# Interfaces.net
KiCad netlist of a schematic drawn in Altium Designer
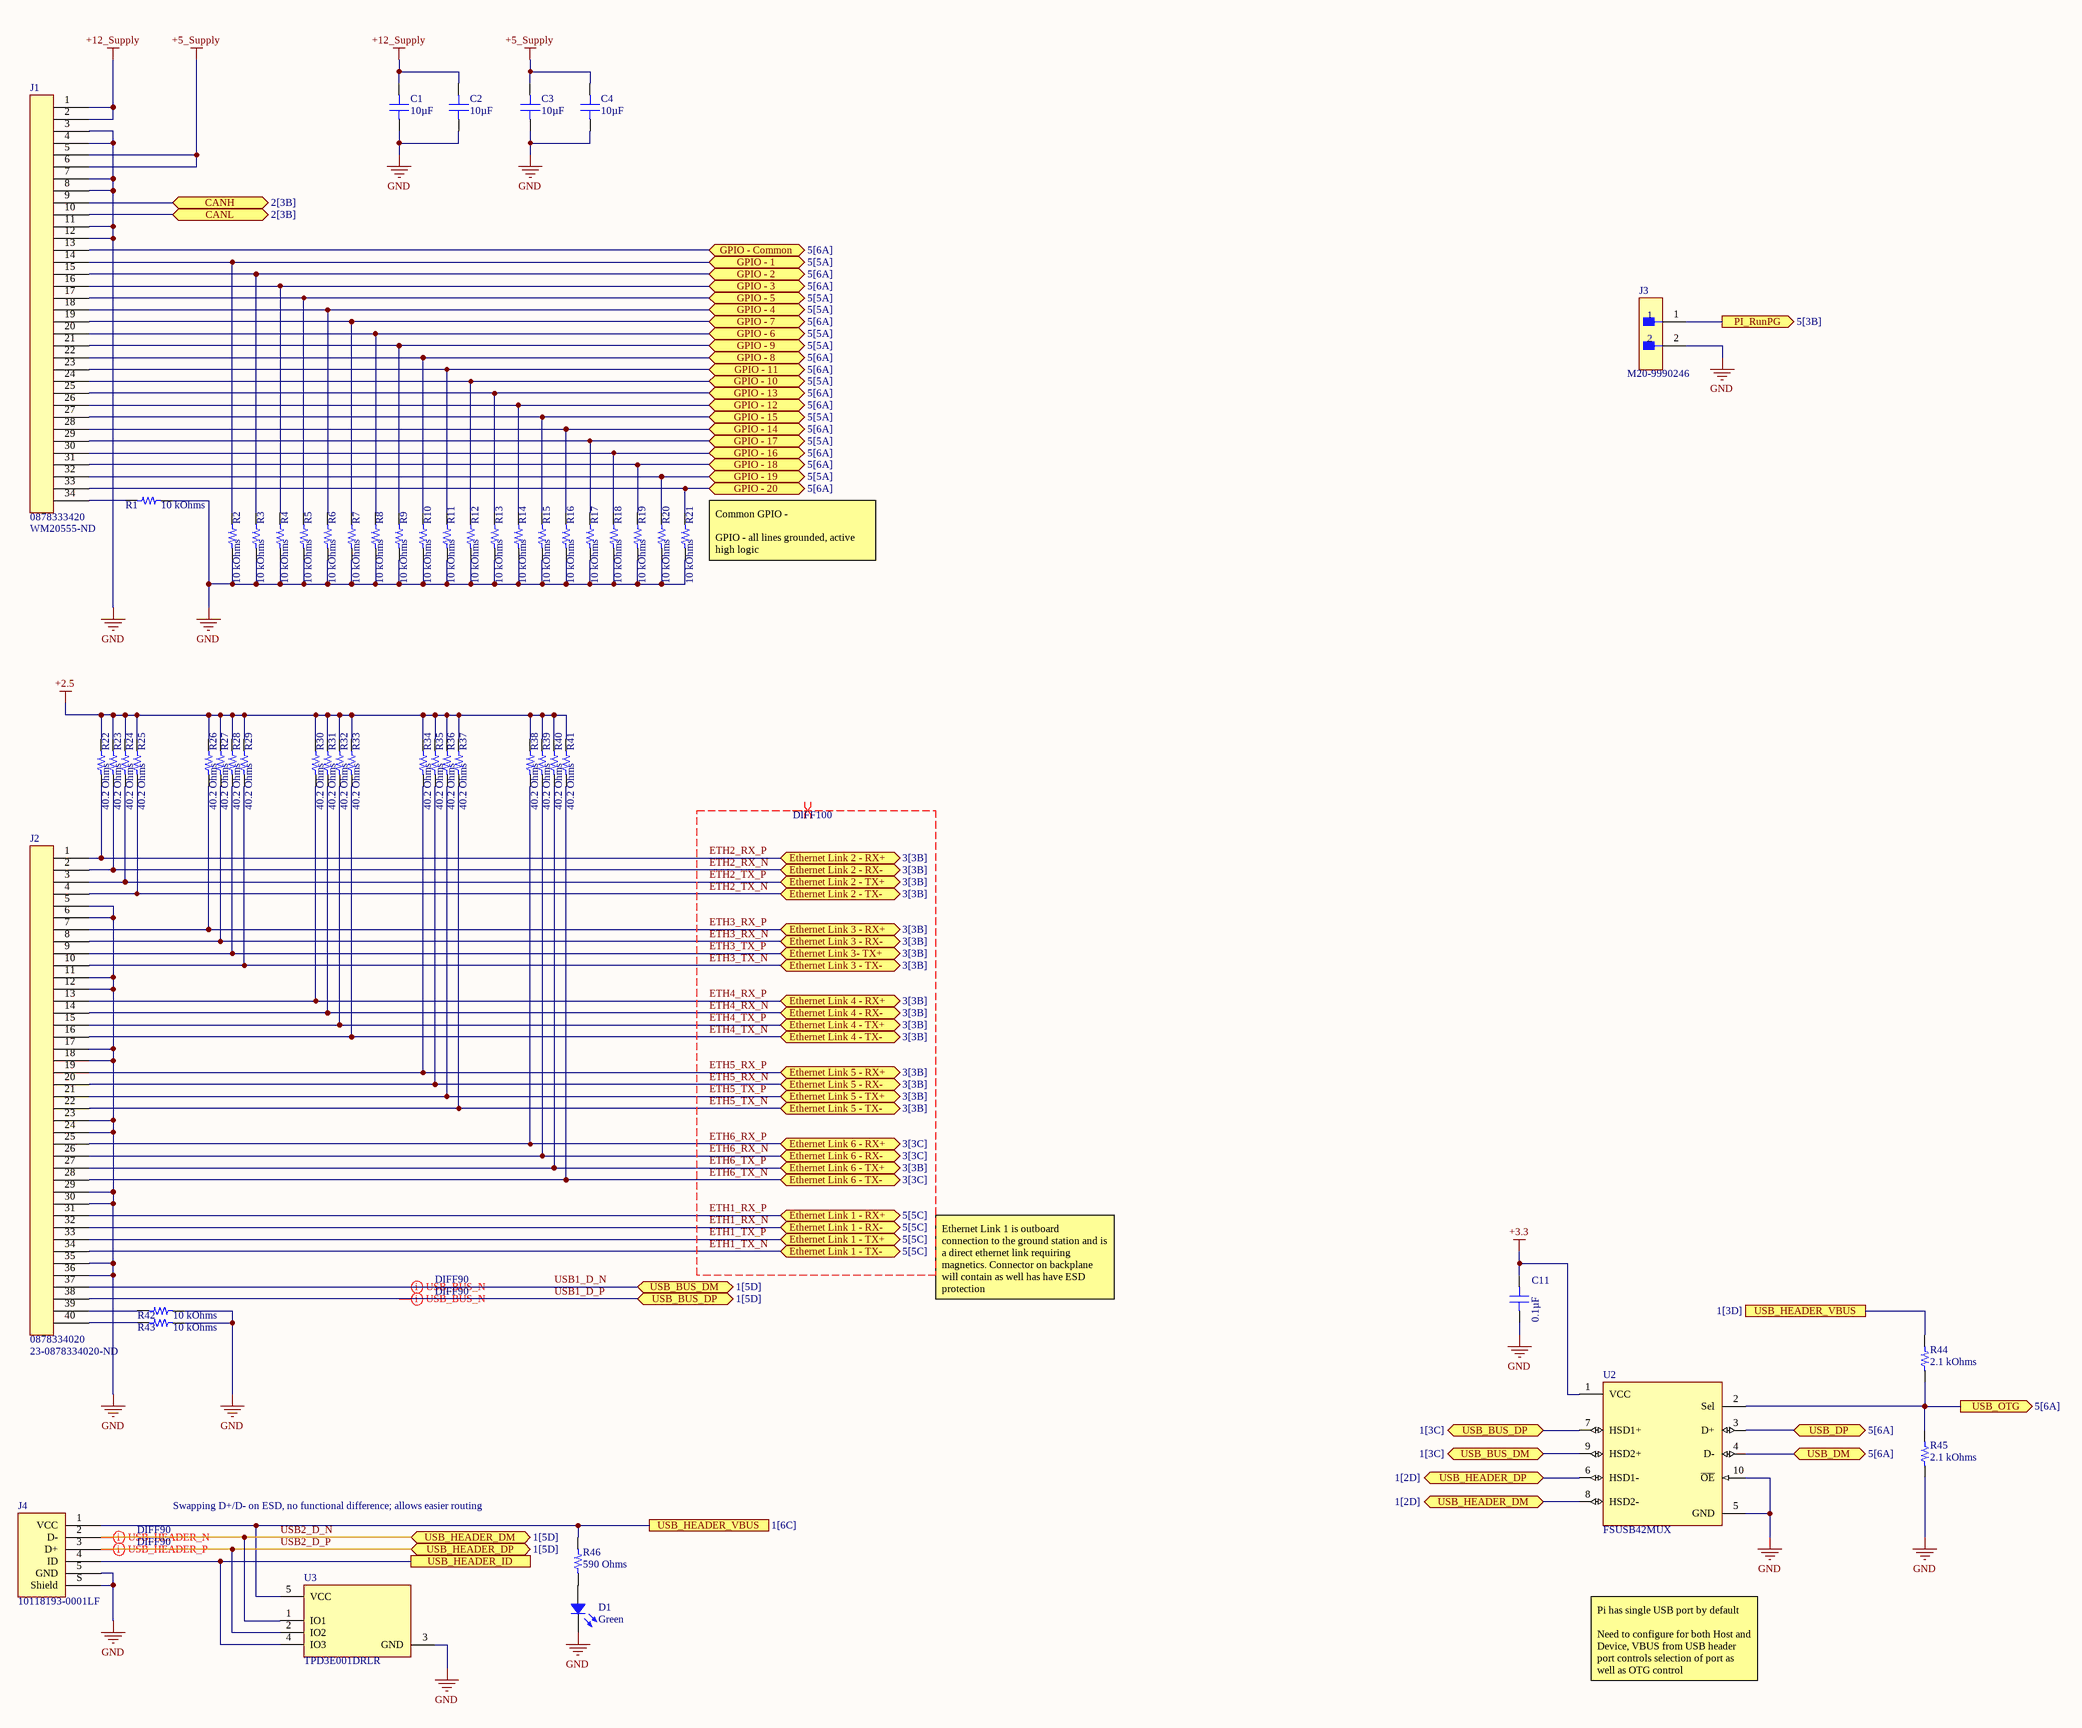
[diagram p0: Interfaces.SchDoc]

(export (version "E")
  (design (tool "Eeschema 10.0.6"))
  (components
    (comp (ref "C1")
      (value "10µF")
      (footprint "CAP 0805_2012")
      (description "CAP CER 10UF 16V X5R 0805")
      (fields (field (name "PART NUMBER") "CC0805KKX5R7BB106") (field (name "MANUFACTURER") "Yageo"))
      (libsource (lib "Celestial Altium Library - altium_library") (part "Capacitor"))
    )
    (comp (ref "C2")
      (value "10µF")
      (footprint "CAP 0805_2012")
      (description "CAP CER 10UF 16V X5R 0805")
      (fields (field (name "PART NUMBER") "CC0805KKX5R7BB106") (field (name "MANUFACTURER") "Yageo"))
      (libsource (lib "Celestial Altium Library - altium_library") (part "Capacitor"))
    )
    (comp (ref "C3")
      (value "10µF")
      (footprint "CAP 0805_2012")
      (description "CAP CER 10UF 16V X5R 0805")
      (fields (field (name "PART NUMBER") "CC0805KKX5R7BB106") (field (name "MANUFACTURER") "Yageo"))
      (libsource (lib "Celestial Altium Library - altium_library") (part "Capacitor"))
    )
    (comp (ref "C4")
      (value "10µF")
      (footprint "CAP 0805_2012")
      (description "CAP CER 10UF 16V X5R 0805")
      (fields (field (name "PART NUMBER") "CC0805KKX5R7BB106") (field (name "MANUFACTURER") "Yageo"))
      (libsource (lib "Celestial Altium Library - altium_library") (part "Capacitor"))
    )
    (comp (ref "C11")
      (value "0.1µF")
      (footprint "CAP 0603_1608")
      (description "CAP CER 0.1UF 25V X7R 0603")
      (fields
        (field (name "PART NUMBER") "CL10B104KA8WPNC")
        (field (name "MANUFACTURER") "Samsung Electro-Mechanics")
      )
      (libsource (lib "Celestial Altium Library - altium_library") (part "Capacitor"))
    )
    (comp (ref "D1")
      (value "Green")
      (footprint "LED 0603_1608 GREEN")
      (description "LED GREEN CLEAR CHIP SMD")
      (fields (field (name "PART NUMBER") "LTST-C193KGKT-5A") (field (name "MANUFACTURER") "Lite-On Inc."))
      (libsource (lib "Celestial Altium Library - altium_library") (part "LED"))
    )
    (comp (ref "J1")
      (value "0878333420")
      (footprint "0878333420")
      (fields (field (name "SUPPLIER PART NUMBER 1") "WM20555-ND"))
      (libsource (lib "HAB_Connectors") (part "0878333420"))
    )
    (comp (ref "J2")
      (value "0878334020")
      (footprint "0878334020")
      (fields (field (name "SUPPLIER PART NUMBER 1") "23-0878334020-ND"))
      (libsource (lib "HAB_Connectors") (part "0878334020"))
    )
    (comp (ref "J3")
      (value "M20-9990246")
      (footprint "FP-M20-9990246-MFG")
      (description "CONN HEADER VERT 2POS 2.54MM")
      (fields
        (field (name "OCTOPART") "https://octopart.com/m20-9990246-harwin-2590635")
        (field (name "MANUFACTURER") "Harwin")
      )
      (libsource (lib "Altium Content Vault") (part "3bc925449376181038e59eaffc5286c"))
    )
    (comp (ref "J4")
      (value "10118193-0001LF")
      (footprint "FCI USB 10118193-0001LF")
      (description "CONN RCPT USB2.0 MICRO B SMD R/A")
      (fields (field (name "MANUFACTURER") "Amphenol ICC (FCI)"))
      (libsource (lib "Celestial Altium Library - altium_library") (part "USB 2.0 Type B Micro"))
    )
    (comp (ref "R1")
      (value "10 kOhms")
      (footprint "RES 0603_1608")
      (description "RES 10K OHM 5% 1/10W 0603")
      (fields
        (field (name "PART NUMBER") "RMCF0603JT10K0")
        (field (name "MANUFACTURER") "Stackpole Electronics Inc")
      )
      (libsource (lib "Celestial Altium Library - altium_library") (part "Resistor"))
    )
    (comp (ref "R2")
      (value "10 kOhms")
      (footprint "RES 0603_1608")
      (description "RES 10K OHM 5% 1/10W 0603")
      (fields
        (field (name "PART NUMBER") "RMCF0603JT10K0")
        (field (name "MANUFACTURER") "Stackpole Electronics Inc")
      )
      (libsource (lib "Celestial Altium Library - altium_library") (part "Resistor"))
    )
    (comp (ref "R3")
      (value "10 kOhms")
      (footprint "RES 0603_1608")
      (description "RES 10K OHM 5% 1/10W 0603")
      (fields
        (field (name "PART NUMBER") "RMCF0603JT10K0")
        (field (name "MANUFACTURER") "Stackpole Electronics Inc")
      )
      (libsource (lib "Celestial Altium Library - altium_library") (part "Resistor"))
    )
    (comp (ref "R4")
      (value "10 kOhms")
      (footprint "RES 0603_1608")
      (description "RES 10K OHM 5% 1/10W 0603")
      (fields
        (field (name "PART NUMBER") "RMCF0603JT10K0")
        (field (name "MANUFACTURER") "Stackpole Electronics Inc")
      )
      (libsource (lib "Celestial Altium Library - altium_library") (part "Resistor"))
    )
    (comp (ref "R5")
      (value "10 kOhms")
      (footprint "RES 0603_1608")
      (description "RES 10K OHM 5% 1/10W 0603")
      (fields
        (field (name "PART NUMBER") "RMCF0603JT10K0")
        (field (name "MANUFACTURER") "Stackpole Electronics Inc")
      )
      (libsource (lib "Celestial Altium Library - altium_library") (part "Resistor"))
    )
    (comp (ref "R6")
      (value "10 kOhms")
      (footprint "RES 0603_1608")
      (description "RES 10K OHM 5% 1/10W 0603")
      (fields
        (field (name "PART NUMBER") "RMCF0603JT10K0")
        (field (name "MANUFACTURER") "Stackpole Electronics Inc")
      )
      (libsource (lib "Celestial Altium Library - altium_library") (part "Resistor"))
    )
    (comp (ref "R7")
      (value "10 kOhms")
      (footprint "RES 0603_1608")
      (description "RES 10K OHM 5% 1/10W 0603")
      (fields
        (field (name "PART NUMBER") "RMCF0603JT10K0")
        (field (name "MANUFACTURER") "Stackpole Electronics Inc")
      )
      (libsource (lib "Celestial Altium Library - altium_library") (part "Resistor"))
    )
    (comp (ref "R8")
      (value "10 kOhms")
      (footprint "RES 0603_1608")
      (description "RES 10K OHM 5% 1/10W 0603")
      (fields
        (field (name "PART NUMBER") "RMCF0603JT10K0")
        (field (name "MANUFACTURER") "Stackpole Electronics Inc")
      )
      (libsource (lib "Celestial Altium Library - altium_library") (part "Resistor"))
    )
    (comp (ref "R9")
      (value "10 kOhms")
      (footprint "RES 0603_1608")
      (description "RES 10K OHM 5% 1/10W 0603")
      (fields
        (field (name "PART NUMBER") "RMCF0603JT10K0")
        (field (name "MANUFACTURER") "Stackpole Electronics Inc")
      )
      (libsource (lib "Celestial Altium Library - altium_library") (part "Resistor"))
    )
    (comp (ref "R10")
      (value "10 kOhms")
      (footprint "RES 0603_1608")
      (description "RES 10K OHM 5% 1/10W 0603")
      (fields
        (field (name "PART NUMBER") "RMCF0603JT10K0")
        (field (name "MANUFACTURER") "Stackpole Electronics Inc")
      )
      (libsource (lib "Celestial Altium Library - altium_library") (part "Resistor"))
    )
    (comp (ref "R11")
      (value "10 kOhms")
      (footprint "RES 0603_1608")
      (description "RES 10K OHM 5% 1/10W 0603")
      (fields
        (field (name "PART NUMBER") "RMCF0603JT10K0")
        (field (name "MANUFACTURER") "Stackpole Electronics Inc")
      )
      (libsource (lib "Celestial Altium Library - altium_library") (part "Resistor"))
    )
    (comp (ref "R12")
      (value "10 kOhms")
      (footprint "RES 0603_1608")
      (description "RES 10K OHM 5% 1/10W 0603")
      (fields
        (field (name "PART NUMBER") "RMCF0603JT10K0")
        (field (name "MANUFACTURER") "Stackpole Electronics Inc")
      )
      (libsource (lib "Celestial Altium Library - altium_library") (part "Resistor"))
    )
    (comp (ref "R13")
      (value "10 kOhms")
      (footprint "RES 0603_1608")
      (description "RES 10K OHM 5% 1/10W 0603")
      (fields
        (field (name "PART NUMBER") "RMCF0603JT10K0")
        (field (name "MANUFACTURER") "Stackpole Electronics Inc")
      )
      (libsource (lib "Celestial Altium Library - altium_library") (part "Resistor"))
    )
    (comp (ref "R14")
      (value "10 kOhms")
      (footprint "RES 0603_1608")
      (description "RES 10K OHM 5% 1/10W 0603")
      (fields
        (field (name "PART NUMBER") "RMCF0603JT10K0")
        (field (name "MANUFACTURER") "Stackpole Electronics Inc")
      )
      (libsource (lib "Celestial Altium Library - altium_library") (part "Resistor"))
    )
    (comp (ref "R15")
      (value "10 kOhms")
      (footprint "RES 0603_1608")
      (description "RES 10K OHM 5% 1/10W 0603")
      (fields
        (field (name "PART NUMBER") "RMCF0603JT10K0")
        (field (name "MANUFACTURER") "Stackpole Electronics Inc")
      )
      (libsource (lib "Celestial Altium Library - altium_library") (part "Resistor"))
    )
    (comp (ref "R16")
      (value "10 kOhms")
      (footprint "RES 0603_1608")
      (description "RES 10K OHM 5% 1/10W 0603")
      (fields
        (field (name "PART NUMBER") "RMCF0603JT10K0")
        (field (name "MANUFACTURER") "Stackpole Electronics Inc")
      )
      (libsource (lib "Celestial Altium Library - altium_library") (part "Resistor"))
    )
    (comp (ref "R17")
      (value "10 kOhms")
      (footprint "RES 0603_1608")
      (description "RES 10K OHM 5% 1/10W 0603")
      (fields
        (field (name "PART NUMBER") "RMCF0603JT10K0")
        (field (name "MANUFACTURER") "Stackpole Electronics Inc")
      )
      (libsource (lib "Celestial Altium Library - altium_library") (part "Resistor"))
    )
    (comp (ref "R18")
      (value "10 kOhms")
      (footprint "RES 0603_1608")
      (description "RES 10K OHM 5% 1/10W 0603")
      (fields
        (field (name "PART NUMBER") "RMCF0603JT10K0")
        (field (name "MANUFACTURER") "Stackpole Electronics Inc")
      )
      (libsource (lib "Celestial Altium Library - altium_library") (part "Resistor"))
    )
    (comp (ref "R19")
      (value "10 kOhms")
      (footprint "RES 0603_1608")
      (description "RES 10K OHM 5% 1/10W 0603")
      (fields
        (field (name "PART NUMBER") "RMCF0603JT10K0")
        (field (name "MANUFACTURER") "Stackpole Electronics Inc")
      )
      (libsource (lib "Celestial Altium Library - altium_library") (part "Resistor"))
    )
    (comp (ref "R20")
      (value "10 kOhms")
      (footprint "RES 0603_1608")
      (description "RES 10K OHM 5% 1/10W 0603")
      (fields
        (field (name "PART NUMBER") "RMCF0603JT10K0")
        (field (name "MANUFACTURER") "Stackpole Electronics Inc")
      )
      (libsource (lib "Celestial Altium Library - altium_library") (part "Resistor"))
    )
    (comp (ref "R21")
      (value "10 kOhms")
      (footprint "RES 0603_1608")
      (description "RES 10K OHM 5% 1/10W 0603")
      (fields
        (field (name "PART NUMBER") "RMCF0603JT10K0")
        (field (name "MANUFACTURER") "Stackpole Electronics Inc")
      )
      (libsource (lib "Celestial Altium Library - altium_library") (part "Resistor"))
    )
    (comp (ref "R22")
      (value "40.2 Ohms")
      (footprint "RES 0603_1608")
      (description "RES SMD 40.2 OHM 1% 1/10W 0603")
      (fields (field (name "PART NUMBER") "RC0603FR-0740R2L") (field (name "MANUFACTURER") "Yageo"))
      (libsource (lib "Celestial Altium Library - altium_library") (part "Resistor"))
    )
    (comp (ref "R23")
      (value "40.2 Ohms")
      (footprint "RES 0603_1608")
      (description "RES SMD 40.2 OHM 1% 1/10W 0603")
      (fields (field (name "PART NUMBER") "RC0603FR-0740R2L") (field (name "MANUFACTURER") "Yageo"))
      (libsource (lib "Celestial Altium Library - altium_library") (part "Resistor"))
    )
    (comp (ref "R24")
      (value "40.2 Ohms")
      (footprint "RES 0603_1608")
      (description "RES SMD 40.2 OHM 1% 1/10W 0603")
      (fields (field (name "PART NUMBER") "RC0603FR-0740R2L") (field (name "MANUFACTURER") "Yageo"))
      (libsource (lib "Celestial Altium Library - altium_library") (part "Resistor"))
    )
    (comp (ref "R25")
      (value "40.2 Ohms")
      (footprint "RES 0603_1608")
      (description "RES SMD 40.2 OHM 1% 1/10W 0603")
      (fields (field (name "PART NUMBER") "RC0603FR-0740R2L") (field (name "MANUFACTURER") "Yageo"))
      (libsource (lib "Celestial Altium Library - altium_library") (part "Resistor"))
    )
    (comp (ref "R26")
      (value "40.2 Ohms")
      (footprint "RES 0603_1608")
      (description "RES SMD 40.2 OHM 1% 1/10W 0603")
      (fields (field (name "PART NUMBER") "RC0603FR-0740R2L") (field (name "MANUFACTURER") "Yageo"))
      (libsource (lib "Celestial Altium Library - altium_library") (part "Resistor"))
    )
    (comp (ref "R27")
      (value "40.2 Ohms")
      (footprint "RES 0603_1608")
      (description "RES SMD 40.2 OHM 1% 1/10W 0603")
      (fields (field (name "PART NUMBER") "RC0603FR-0740R2L") (field (name "MANUFACTURER") "Yageo"))
      (libsource (lib "Celestial Altium Library - altium_library") (part "Resistor"))
    )
    (comp (ref "R28")
      (value "40.2 Ohms")
      (footprint "RES 0603_1608")
      (description "RES SMD 40.2 OHM 1% 1/10W 0603")
      (fields (field (name "PART NUMBER") "RC0603FR-0740R2L") (field (name "MANUFACTURER") "Yageo"))
      (libsource (lib "Celestial Altium Library - altium_library") (part "Resistor"))
    )
    (comp (ref "R29")
      (value "40.2 Ohms")
      (footprint "RES 0603_1608")
      (description "RES SMD 40.2 OHM 1% 1/10W 0603")
      (fields (field (name "PART NUMBER") "RC0603FR-0740R2L") (field (name "MANUFACTURER") "Yageo"))
      (libsource (lib "Celestial Altium Library - altium_library") (part "Resistor"))
    )
    (comp (ref "R30")
      (value "40.2 Ohms")
      (footprint "RES 0603_1608")
      (description "RES SMD 40.2 OHM 1% 1/10W 0603")
      (fields (field (name "PART NUMBER") "RC0603FR-0740R2L") (field (name "MANUFACTURER") "Yageo"))
      (libsource (lib "Celestial Altium Library - altium_library") (part "Resistor"))
    )
    (comp (ref "R31")
      (value "40.2 Ohms")
      (footprint "RES 0603_1608")
      (description "RES SMD 40.2 OHM 1% 1/10W 0603")
      (fields (field (name "PART NUMBER") "RC0603FR-0740R2L") (field (name "MANUFACTURER") "Yageo"))
      (libsource (lib "Celestial Altium Library - altium_library") (part "Resistor"))
    )
    (comp (ref "R32")
      (value "40.2 Ohms")
      (footprint "RES 0603_1608")
      (description "RES SMD 40.2 OHM 1% 1/10W 0603")
      (fields (field (name "PART NUMBER") "RC0603FR-0740R2L") (field (name "MANUFACTURER") "Yageo"))
      (libsource (lib "Celestial Altium Library - altium_library") (part "Resistor"))
    )
    (comp (ref "R33")
      (value "40.2 Ohms")
      (footprint "RES 0603_1608")
      (description "RES SMD 40.2 OHM 1% 1/10W 0603")
      (fields (field (name "PART NUMBER") "RC0603FR-0740R2L") (field (name "MANUFACTURER") "Yageo"))
      (libsource (lib "Celestial Altium Library - altium_library") (part "Resistor"))
    )
    (comp (ref "R34")
      (value "40.2 Ohms")
      (footprint "RES 0603_1608")
      (description "RES SMD 40.2 OHM 1% 1/10W 0603")
      (fields (field (name "PART NUMBER") "RC0603FR-0740R2L") (field (name "MANUFACTURER") "Yageo"))
      (libsource (lib "Celestial Altium Library - altium_library") (part "Resistor"))
    )
    (comp (ref "R35")
      (value "40.2 Ohms")
      (footprint "RES 0603_1608")
      (description "RES SMD 40.2 OHM 1% 1/10W 0603")
      (fields (field (name "PART NUMBER") "RC0603FR-0740R2L") (field (name "MANUFACTURER") "Yageo"))
      (libsource (lib "Celestial Altium Library - altium_library") (part "Resistor"))
    )
    (comp (ref "R36")
      (value "40.2 Ohms")
      (footprint "RES 0603_1608")
      (description "RES SMD 40.2 OHM 1% 1/10W 0603")
      (fields (field (name "PART NUMBER") "RC0603FR-0740R2L") (field (name "MANUFACTURER") "Yageo"))
      (libsource (lib "Celestial Altium Library - altium_library") (part "Resistor"))
    )
    (comp (ref "R37")
      (value "40.2 Ohms")
      (footprint "RES 0603_1608")
      (description "RES SMD 40.2 OHM 1% 1/10W 0603")
      (fields (field (name "PART NUMBER") "RC0603FR-0740R2L") (field (name "MANUFACTURER") "Yageo"))
      (libsource (lib "Celestial Altium Library - altium_library") (part "Resistor"))
    )
    (comp (ref "R38")
      (value "40.2 Ohms")
      (footprint "RES 0603_1608")
      (description "RES SMD 40.2 OHM 1% 1/10W 0603")
      (fields (field (name "PART NUMBER") "RC0603FR-0740R2L") (field (name "MANUFACTURER") "Yageo"))
      (libsource (lib "Celestial Altium Library - altium_library") (part "Resistor"))
    )
    (comp (ref "R39")
      (value "40.2 Ohms")
      (footprint "RES 0603_1608")
      (description "RES SMD 40.2 OHM 1% 1/10W 0603")
      (fields (field (name "PART NUMBER") "RC0603FR-0740R2L") (field (name "MANUFACTURER") "Yageo"))
      (libsource (lib "Celestial Altium Library - altium_library") (part "Resistor"))
    )
    (comp (ref "R40")
      (value "40.2 Ohms")
      (footprint "RES 0603_1608")
      (description "RES SMD 40.2 OHM 1% 1/10W 0603")
      (fields (field (name "PART NUMBER") "RC0603FR-0740R2L") (field (name "MANUFACTURER") "Yageo"))
      (libsource (lib "Celestial Altium Library - altium_library") (part "Resistor"))
    )
    (comp (ref "R41")
      (value "40.2 Ohms")
      (footprint "RES 0603_1608")
      (description "RES SMD 40.2 OHM 1% 1/10W 0603")
      (fields (field (name "PART NUMBER") "RC0603FR-0740R2L") (field (name "MANUFACTURER") "Yageo"))
      (libsource (lib "Celestial Altium Library - altium_library") (part "Resistor"))
    )
    (comp (ref "R42")
      (value "10 kOhms")
      (footprint "RES 0603_1608")
      (description "RES 10K OHM 5% 1/10W 0603")
      (fields
        (field (name "PART NUMBER") "RMCF0603JT10K0")
        (field (name "MANUFACTURER") "Stackpole Electronics Inc")
      )
      (libsource (lib "Celestial Altium Library - altium_library") (part "Resistor"))
    )
    (comp (ref "R43")
      (value "10 kOhms")
      (footprint "RES 0603_1608")
      (description "RES 10K OHM 5% 1/10W 0603")
      (fields
        (field (name "PART NUMBER") "RMCF0603JT10K0")
        (field (name "MANUFACTURER") "Stackpole Electronics Inc")
      )
      (libsource (lib "Celestial Altium Library - altium_library") (part "Resistor"))
    )
    (comp (ref "R44")
      (value "2.1 kOhms")
      (footprint "RES 0603_1608")
      (description "RES 2.1K OHM 1% 1/10W 0603")
      (fields
        (field (name "PART NUMBER") "RMCF0603FT2K10")
        (field (name "MANUFACTURER") "Stackpole Electronics Inc")
      )
      (libsource (lib "Celestial Altium Library - altium_library") (part "Resistor"))
    )
    (comp (ref "R45")
      (value "2.1 kOhms")
      (footprint "RES 0603_1608")
      (description "RES 2.1K OHM 1% 1/10W 0603")
      (fields
        (field (name "PART NUMBER") "RMCF0603FT2K10")
        (field (name "MANUFACTURER") "Stackpole Electronics Inc")
      )
      (libsource (lib "Celestial Altium Library - altium_library") (part "Resistor"))
    )
    (comp (ref "R46")
      (value "590 Ohms")
      (footprint "RES 0603_1608")
      (description "RES 590 OHM 1% 1/10W 0603")
      (fields
        (field (name "PART NUMBER") "RMCF0603FT590R")
        (field (name "MANUFACTURER") "Stackpole Electronics Inc")
      )
      (libsource (lib "Celestial Altium Library - altium_library") (part "Resistor"))
    )
    (comp (ref "U2")
      (value "FSUSB42MUX")
      (footprint "FP-846AP-MFG")
      (description "IC USB SWITCH DPDT 10MSOP")
      (fields (field (name "VOLTAGE") "4.3V"))
      (libsource (lib "Altium Content Vault") (part "e0bd5e1b4e0e4edc77f3356c64bf8f9"))
    )
    (comp (ref "U3")
      (value "TPD3E001DRLR")
      (footprint "FP-DRL0005A-MFG")
      (description "TVS DIODE 5.5V SOT5")
      (libsource (lib "Altium Content Vault") (part "867ba43d99b3a33c275ad84274a843c"))
    )
  )
  (nets
    (net (code "1") (name "+2.5") (class "Default")
      (node (ref "R22") (pin "2") (pinfunction "2_2") (pintype "passive"))
      (node (ref "R23") (pin "2") (pinfunction "2_2") (pintype "passive"))
      (node (ref "R24") (pin "2") (pinfunction "2_2") (pintype "passive"))
      (node (ref "R25") (pin "2") (pinfunction "2_2") (pintype "passive"))
      (node (ref "R26") (pin "2") (pinfunction "2_2") (pintype "passive"))
      (node (ref "R27") (pin "2") (pinfunction "2_2") (pintype "passive"))
      (node (ref "R28") (pin "2") (pinfunction "2_2") (pintype "passive"))
      (node (ref "R29") (pin "2") (pinfunction "2_2") (pintype "passive"))
      (node (ref "R30") (pin "2") (pinfunction "2_2") (pintype "passive"))
      (node (ref "R31") (pin "2") (pinfunction "2_2") (pintype "passive"))
      (node (ref "R32") (pin "2") (pinfunction "2_2") (pintype "passive"))
      (node (ref "R33") (pin "2") (pinfunction "2_2") (pintype "passive"))
      (node (ref "R34") (pin "2") (pinfunction "2_2") (pintype "passive"))
      (node (ref "R35") (pin "2") (pinfunction "2_2") (pintype "passive"))
      (node (ref "R36") (pin "2") (pinfunction "2_2") (pintype "passive"))
      (node (ref "R37") (pin "2") (pinfunction "2_2") (pintype "passive"))
      (node (ref "R38") (pin "2") (pinfunction "2_2") (pintype "passive"))
      (node (ref "R39") (pin "2") (pinfunction "2_2") (pintype "passive"))
      (node (ref "R40") (pin "2") (pinfunction "2_2") (pintype "passive"))
      (node (ref "R41") (pin "2") (pinfunction "2_2") (pintype "passive"))
    )
    (net (code "2") (name "+3.3") (class "Default")
      (node (ref "C11") (pin "2") (pinfunction "2_2") (pintype "passive"))
      (node (ref "U2") (pin "1") (pinfunction "VCC_1") (pintype "power_in"))
    )
    (net (code "3") (name "+5_Supply") (class "Default")
      (node (ref "C3") (pin "2") (pinfunction "2_2") (pintype "passive"))
      (node (ref "C4") (pin "2") (pinfunction "2_2") (pintype "passive"))
      (node (ref "J1") (pin "5") (pintype "passive"))
      (node (ref "J1") (pin "6") (pintype "passive"))
    )
    (net (code "4") (name "+12_Supply") (class "Default")
      (node (ref "C1") (pin "2") (pinfunction "2_2") (pintype "passive"))
      (node (ref "C2") (pin "2") (pinfunction "2_2") (pintype "passive"))
      (node (ref "J1") (pin "1") (pintype "passive"))
      (node (ref "J1") (pin "2") (pintype "passive"))
    )
    (net (code "5") (name "/CANH") (class "Default") (node (ref "J1") (pin "9") (pintype "passive")))
    (net (code "6") (name "/CANL") (class "Default") (node (ref "J1") (pin "10") (pintype "passive")))
    (net (code "7") (name "/ETH1_RX_N") (class "Default") (node (ref "J2") (pin "32") (pintype "passive")))
    (net (code "8") (name "/ETH1_RX_P") (class "Default") (node (ref "J2") (pin "31") (pintype "passive")))
    (net (code "9") (name "/ETH1_TX_N") (class "Default") (node (ref "J2") (pin "34") (pintype "passive")))
    (net (code "10") (name "/ETH1_TX_P") (class "Default") (node (ref "J2") (pin "33") (pintype "passive")))
    (net (code "11") (name "/ETH2_RX_N") (class "Default")
      (node (ref "J2") (pin "2") (pintype "passive"))
      (node (ref "R23") (pin "1") (pinfunction "1_1") (pintype "passive"))
    )
    (net (code "12") (name "/ETH2_RX_P") (class "Default")
      (node (ref "J2") (pin "1") (pintype "passive"))
      (node (ref "R22") (pin "1") (pinfunction "1_1") (pintype "passive"))
    )
    (net (code "13") (name "/ETH2_TX_N") (class "Default")
      (node (ref "J2") (pin "4") (pintype "passive"))
      (node (ref "R25") (pin "1") (pinfunction "1_1") (pintype "passive"))
    )
    (net (code "14") (name "/ETH2_TX_P") (class "Default")
      (node (ref "J2") (pin "3") (pintype "passive"))
      (node (ref "R24") (pin "1") (pinfunction "1_1") (pintype "passive"))
    )
    (net (code "15") (name "/ETH3_RX_N") (class "Default")
      (node (ref "J2") (pin "8") (pintype "passive"))
      (node (ref "R27") (pin "1") (pinfunction "1_1") (pintype "passive"))
    )
    (net (code "16") (name "/ETH3_RX_P") (class "Default")
      (node (ref "J2") (pin "7") (pintype "passive"))
      (node (ref "R26") (pin "1") (pinfunction "1_1") (pintype "passive"))
    )
    (net (code "17") (name "/ETH3_TX_N") (class "Default")
      (node (ref "J2") (pin "10") (pintype "passive"))
      (node (ref "R29") (pin "1") (pinfunction "1_1") (pintype "passive"))
    )
    (net (code "18") (name "/ETH3_TX_P") (class "Default")
      (node (ref "J2") (pin "9") (pintype "passive"))
      (node (ref "R28") (pin "1") (pinfunction "1_1") (pintype "passive"))
    )
    (net (code "19") (name "/ETH4_RX_N") (class "Default")
      (node (ref "J2") (pin "14") (pintype "passive"))
      (node (ref "R31") (pin "1") (pinfunction "1_1") (pintype "passive"))
    )
    (net (code "20") (name "/ETH4_RX_P") (class "Default")
      (node (ref "J2") (pin "13") (pintype "passive"))
      (node (ref "R30") (pin "1") (pinfunction "1_1") (pintype "passive"))
    )
    (net (code "21") (name "/ETH4_TX_N") (class "Default")
      (node (ref "J2") (pin "16") (pintype "passive"))
      (node (ref "R33") (pin "1") (pinfunction "1_1") (pintype "passive"))
    )
    (net (code "22") (name "/ETH4_TX_P") (class "Default")
      (node (ref "J2") (pin "15") (pintype "passive"))
      (node (ref "R32") (pin "1") (pinfunction "1_1") (pintype "passive"))
    )
    (net (code "23") (name "/ETH5_RX_N") (class "Default")
      (node (ref "J2") (pin "20") (pintype "passive"))
      (node (ref "R35") (pin "1") (pinfunction "1_1") (pintype "passive"))
    )
    (net (code "24") (name "/ETH5_RX_P") (class "Default")
      (node (ref "J2") (pin "19") (pintype "passive"))
      (node (ref "R34") (pin "1") (pinfunction "1_1") (pintype "passive"))
    )
    (net (code "25") (name "/ETH5_TX_N") (class "Default")
      (node (ref "J2") (pin "22") (pintype "passive"))
      (node (ref "R37") (pin "1") (pinfunction "1_1") (pintype "passive"))
    )
    (net (code "26") (name "/ETH5_TX_P") (class "Default")
      (node (ref "J2") (pin "21") (pintype "passive"))
      (node (ref "R36") (pin "1") (pinfunction "1_1") (pintype "passive"))
    )
    (net (code "27") (name "/ETH6_RX_N") (class "Default")
      (node (ref "J2") (pin "26") (pintype "passive"))
      (node (ref "R39") (pin "1") (pinfunction "1_1") (pintype "passive"))
    )
    (net (code "28") (name "/ETH6_RX_P") (class "Default")
      (node (ref "J2") (pin "25") (pintype "passive"))
      (node (ref "R38") (pin "1") (pinfunction "1_1") (pintype "passive"))
    )
    (net (code "29") (name "/ETH6_TX_N") (class "Default")
      (node (ref "J2") (pin "28") (pintype "passive"))
      (node (ref "R41") (pin "1") (pinfunction "1_1") (pintype "passive"))
    )
    (net (code "30") (name "/ETH6_TX_P") (class "Default")
      (node (ref "J2") (pin "27") (pintype "passive"))
      (node (ref "R40") (pin "1") (pinfunction "1_1") (pintype "passive"))
    )
    (net (code "31") (name "/GPIO - 1") (class "Default")
      (node (ref "J1") (pin "14") (pintype "passive"))
      (node (ref "R2") (pin "2") (pinfunction "2_2") (pintype "passive"))
    )
    (net (code "32") (name "/GPIO - 2") (class "Default")
      (node (ref "J1") (pin "15") (pintype "passive"))
      (node (ref "R3") (pin "2") (pinfunction "2_2") (pintype "passive"))
    )
    (net (code "33") (name "/GPIO - 3") (class "Default")
      (node (ref "J1") (pin "16") (pintype "passive"))
      (node (ref "R4") (pin "2") (pinfunction "2_2") (pintype "passive"))
    )
    (net (code "34") (name "/GPIO - 4") (class "Default")
      (node (ref "J1") (pin "18") (pintype "passive"))
      (node (ref "R6") (pin "2") (pinfunction "2_2") (pintype "passive"))
    )
    (net (code "35") (name "/GPIO - 5") (class "Default")
      (node (ref "J1") (pin "17") (pintype "passive"))
      (node (ref "R5") (pin "2") (pinfunction "2_2") (pintype "passive"))
    )
    (net (code "36") (name "/GPIO - 6") (class "Default")
      (node (ref "J1") (pin "20") (pintype "passive"))
      (node (ref "R8") (pin "2") (pinfunction "2_2") (pintype "passive"))
    )
    (net (code "37") (name "/GPIO - 7") (class "Default")
      (node (ref "J1") (pin "19") (pintype "passive"))
      (node (ref "R7") (pin "2") (pinfunction "2_2") (pintype "passive"))
    )
    (net (code "38") (name "/GPIO - 8") (class "Default")
      (node (ref "J1") (pin "22") (pintype "passive"))
      (node (ref "R10") (pin "2") (pinfunction "2_2") (pintype "passive"))
    )
    (net (code "39") (name "/GPIO - 9") (class "Default")
      (node (ref "J1") (pin "21") (pintype "passive"))
      (node (ref "R9") (pin "2") (pinfunction "2_2") (pintype "passive"))
    )
    (net (code "40") (name "/GPIO - 10") (class "Default")
      (node (ref "J1") (pin "24") (pintype "passive"))
      (node (ref "R12") (pin "2") (pinfunction "2_2") (pintype "passive"))
    )
    (net (code "41") (name "/GPIO - 11") (class "Default")
      (node (ref "J1") (pin "23") (pintype "passive"))
      (node (ref "R11") (pin "2") (pinfunction "2_2") (pintype "passive"))
    )
    (net (code "42") (name "/GPIO - 12") (class "Default")
      (node (ref "J1") (pin "26") (pintype "passive"))
      (node (ref "R14") (pin "2") (pinfunction "2_2") (pintype "passive"))
    )
    (net (code "43") (name "/GPIO - 13") (class "Default")
      (node (ref "J1") (pin "25") (pintype "passive"))
      (node (ref "R13") (pin "2") (pinfunction "2_2") (pintype "passive"))
    )
    (net (code "44") (name "/GPIO - 14") (class "Default")
      (node (ref "J1") (pin "28") (pintype "passive"))
      (node (ref "R16") (pin "2") (pinfunction "2_2") (pintype "passive"))
    )
    (net (code "45") (name "/GPIO - 15") (class "Default")
      (node (ref "J1") (pin "27") (pintype "passive"))
      (node (ref "R15") (pin "2") (pinfunction "2_2") (pintype "passive"))
    )
    (net (code "46") (name "/GPIO - 16") (class "Default")
      (node (ref "J1") (pin "30") (pintype "passive"))
      (node (ref "R18") (pin "2") (pinfunction "2_2") (pintype "passive"))
    )
    (net (code "47") (name "/GPIO - 17") (class "Default")
      (node (ref "J1") (pin "29") (pintype "passive"))
      (node (ref "R17") (pin "2") (pinfunction "2_2") (pintype "passive"))
    )
    (net (code "48") (name "/GPIO - 18") (class "Default")
      (node (ref "J1") (pin "31") (pintype "passive"))
      (node (ref "R19") (pin "2") (pinfunction "2_2") (pintype "passive"))
    )
    (net (code "49") (name "/GPIO - 19") (class "Default")
      (node (ref "J1") (pin "32") (pintype "passive"))
      (node (ref "R20") (pin "2") (pinfunction "2_2") (pintype "passive"))
    )
    (net (code "50") (name "/GPIO - 20") (class "Default")
      (node (ref "J1") (pin "33") (pintype "passive"))
      (node (ref "R21") (pin "2") (pinfunction "2_2") (pintype "passive"))
    )
    (net (code "51") (name "/GPIO - Common") (class "Default")
      (node (ref "J1") (pin "13") (pintype "passive"))
    )
    (net (code "52") (name "/PI_RunPG") (class "Default")
      (node (ref "J3") (pin "1") (pinfunction "1_1") (pintype "passive"))
    )
    (net (code "53") (name "/USB1_D_N") (class "Default")
      (node (ref "J2") (pin "37") (pintype "passive"))
      (node (ref "U2") (pin "9") (pinfunction "HSD2+_9") (pintype "bidirectional"))
    )
    (net (code "54") (name "/USB1_D_P") (class "Default")
      (node (ref "J2") (pin "38") (pintype "passive"))
      (node (ref "U2") (pin "7") (pinfunction "HSD1+_7") (pintype "bidirectional"))
    )
    (net (code "55") (name "/USB2_D_N") (class "Default")
      (node (ref "J4") (pin "2") (pinfunction "D-_2") (pintype "passive"))
      (node (ref "U2") (pin "8") (pinfunction "HSD2-_8") (pintype "bidirectional"))
      (node (ref "U3") (pin "1") (pinfunction "IO1_1") (pintype "passive"))
    )
    (net (code "56") (name "/USB2_D_P") (class "Default")
      (node (ref "J4") (pin "3") (pinfunction "D+_3") (pintype "passive"))
      (node (ref "U2") (pin "6") (pinfunction "HSD1-_6") (pintype "bidirectional"))
      (node (ref "U3") (pin "2") (pinfunction "IO2_2") (pintype "passive"))
    )
    (net (code "57") (name "/USB_DM") (class "Default")
      (node (ref "U2") (pin "4") (pinfunction "D-_4") (pintype "bidirectional"))
    )
    (net (code "58") (name "/USB_DP") (class "Default")
      (node (ref "U2") (pin "3") (pinfunction "D+_3") (pintype "bidirectional"))
    )
    (net (code "59") (name "/USB_HEADER_ID") (class "Default")
      (node (ref "J4") (pin "4") (pinfunction "ID_4") (pintype "passive"))
      (node (ref "U3") (pin "4") (pinfunction "IO3_4") (pintype "passive"))
    )
    (net (code "60") (name "/USB_HEADER_VBUS") (class "Default")
      (node (ref "J4") (pin "1") (pinfunction "VCC_1") (pintype "passive"))
      (node (ref "R44") (pin "2") (pinfunction "2_2") (pintype "passive"))
      (node (ref "R46") (pin "2") (pinfunction "2_2") (pintype "passive"))
      (node (ref "U3") (pin "5") (pinfunction "VCC_5") (pintype "power_in"))
    )
    (net (code "61") (name "/USB_OTG") (class "Default")
      (node (ref "R44") (pin "1") (pinfunction "1_1") (pintype "passive"))
      (node (ref "R45") (pin "2") (pinfunction "2_2") (pintype "passive"))
      (node (ref "U2") (pin "2") (pinfunction "Sel_2") (pintype "passive"))
    )
    (net (code "62") (name "GND") (class "Default")
      (node (ref "C1") (pin "1") (pinfunction "1_1") (pintype "passive"))
      (node (ref "C11") (pin "1") (pinfunction "1_1") (pintype "passive"))
      (node (ref "C2") (pin "1") (pinfunction "1_1") (pintype "passive"))
      (node (ref "C3") (pin "1") (pinfunction "1_1") (pintype "passive"))
      (node (ref "C4") (pin "1") (pinfunction "1_1") (pintype "passive"))
      (node (ref "D1") (pin "2") (pinfunction "2_2") (pintype "passive"))
      (node (ref "J1") (pin "11") (pintype "passive"))
      (node (ref "J1") (pin "12") (pintype "passive"))
      (node (ref "J1") (pin "3") (pintype "passive"))
      (node (ref "J1") (pin "4") (pintype "passive"))
      (node (ref "J1") (pin "7") (pintype "passive"))
      (node (ref "J1") (pin "8") (pintype "passive"))
      (node (ref "J2") (pin "11") (pintype "passive"))
      (node (ref "J2") (pin "12") (pintype "passive"))
      (node (ref "J2") (pin "17") (pintype "passive"))
      (node (ref "J2") (pin "18") (pintype "passive"))
      (node (ref "J2") (pin "23") (pintype "passive"))
      (node (ref "J2") (pin "24") (pintype "passive"))
      (node (ref "J2") (pin "29") (pintype "passive"))
      (node (ref "J2") (pin "30") (pintype "passive"))
      (node (ref "J2") (pin "35") (pintype "passive"))
      (node (ref "J2") (pin "36") (pintype "passive"))
      (node (ref "J2") (pin "5") (pintype "passive"))
      (node (ref "J2") (pin "6") (pintype "passive"))
      (node (ref "J3") (pin "2") (pinfunction "2_2") (pintype "passive"))
      (node (ref "J4") (pin "5") (pinfunction "GND_5") (pintype "passive"))
      (node (ref "J4") (pin "S") (pinfunction "Shield_S") (pintype "passive"))
      (node (ref "R1") (pin "2") (pinfunction "2_2") (pintype "passive"))
      (node (ref "R10") (pin "1") (pinfunction "1_1") (pintype "passive"))
      (node (ref "R11") (pin "1") (pinfunction "1_1") (pintype "passive"))
      (node (ref "R12") (pin "1") (pinfunction "1_1") (pintype "passive"))
      (node (ref "R13") (pin "1") (pinfunction "1_1") (pintype "passive"))
      (node (ref "R14") (pin "1") (pinfunction "1_1") (pintype "passive"))
      (node (ref "R15") (pin "1") (pinfunction "1_1") (pintype "passive"))
      (node (ref "R16") (pin "1") (pinfunction "1_1") (pintype "passive"))
      (node (ref "R17") (pin "1") (pinfunction "1_1") (pintype "passive"))
      (node (ref "R18") (pin "1") (pinfunction "1_1") (pintype "passive"))
      (node (ref "R19") (pin "1") (pinfunction "1_1") (pintype "passive"))
      (node (ref "R2") (pin "1") (pinfunction "1_1") (pintype "passive"))
      (node (ref "R20") (pin "1") (pinfunction "1_1") (pintype "passive"))
      (node (ref "R21") (pin "1") (pinfunction "1_1") (pintype "passive"))
      (node (ref "R3") (pin "1") (pinfunction "1_1") (pintype "passive"))
      (node (ref "R4") (pin "1") (pinfunction "1_1") (pintype "passive"))
      (node (ref "R42") (pin "2") (pinfunction "2_2") (pintype "passive"))
      (node (ref "R43") (pin "2") (pinfunction "2_2") (pintype "passive"))
      (node (ref "R45") (pin "1") (pinfunction "1_1") (pintype "passive"))
      (node (ref "R5") (pin "1") (pinfunction "1_1") (pintype "passive"))
      (node (ref "R6") (pin "1") (pinfunction "1_1") (pintype "passive"))
      (node (ref "R7") (pin "1") (pinfunction "1_1") (pintype "passive"))
      (node (ref "R8") (pin "1") (pinfunction "1_1") (pintype "passive"))
      (node (ref "R9") (pin "1") (pinfunction "1_1") (pintype "passive"))
      (node (ref "U2") (pin "10") (pinfunction "~{OE}_10") (pintype "input"))
      (node (ref "U2") (pin "5") (pinfunction "GND_5") (pintype "power_in"))
      (node (ref "U3") (pin "3") (pinfunction "GND_3") (pintype "power_in"))
    )
    (net (code "63") (name "Net-(D1-Pad1)") (class "Default")
      (node (ref "D1") (pin "1") (pinfunction "1_1") (pintype "passive"))
      (node (ref "R46") (pin "1") (pinfunction "1_1") (pintype "passive"))
    )
    (net (code "64") (name "Net-(J1-Pad34)") (class "Default")
      (node (ref "J1") (pin "34") (pintype "passive"))
      (node (ref "R1") (pin "1") (pinfunction "1_1") (pintype "passive"))
    )
    (net (code "65") (name "Net-(J2-Pad39)") (class "Default")
      (node (ref "J2") (pin "39") (pintype "passive"))
      (node (ref "R42") (pin "1") (pinfunction "1_1") (pintype "passive"))
    )
    (net (code "66") (name "Net-(J2-Pad40)") (class "Default")
      (node (ref "J2") (pin "40") (pintype "passive"))
      (node (ref "R43") (pin "1") (pinfunction "1_1") (pintype "passive"))
    )
  )
)
